# Booster_TOP.net
KiCad netlist of a schematic drawn in Altium Designer
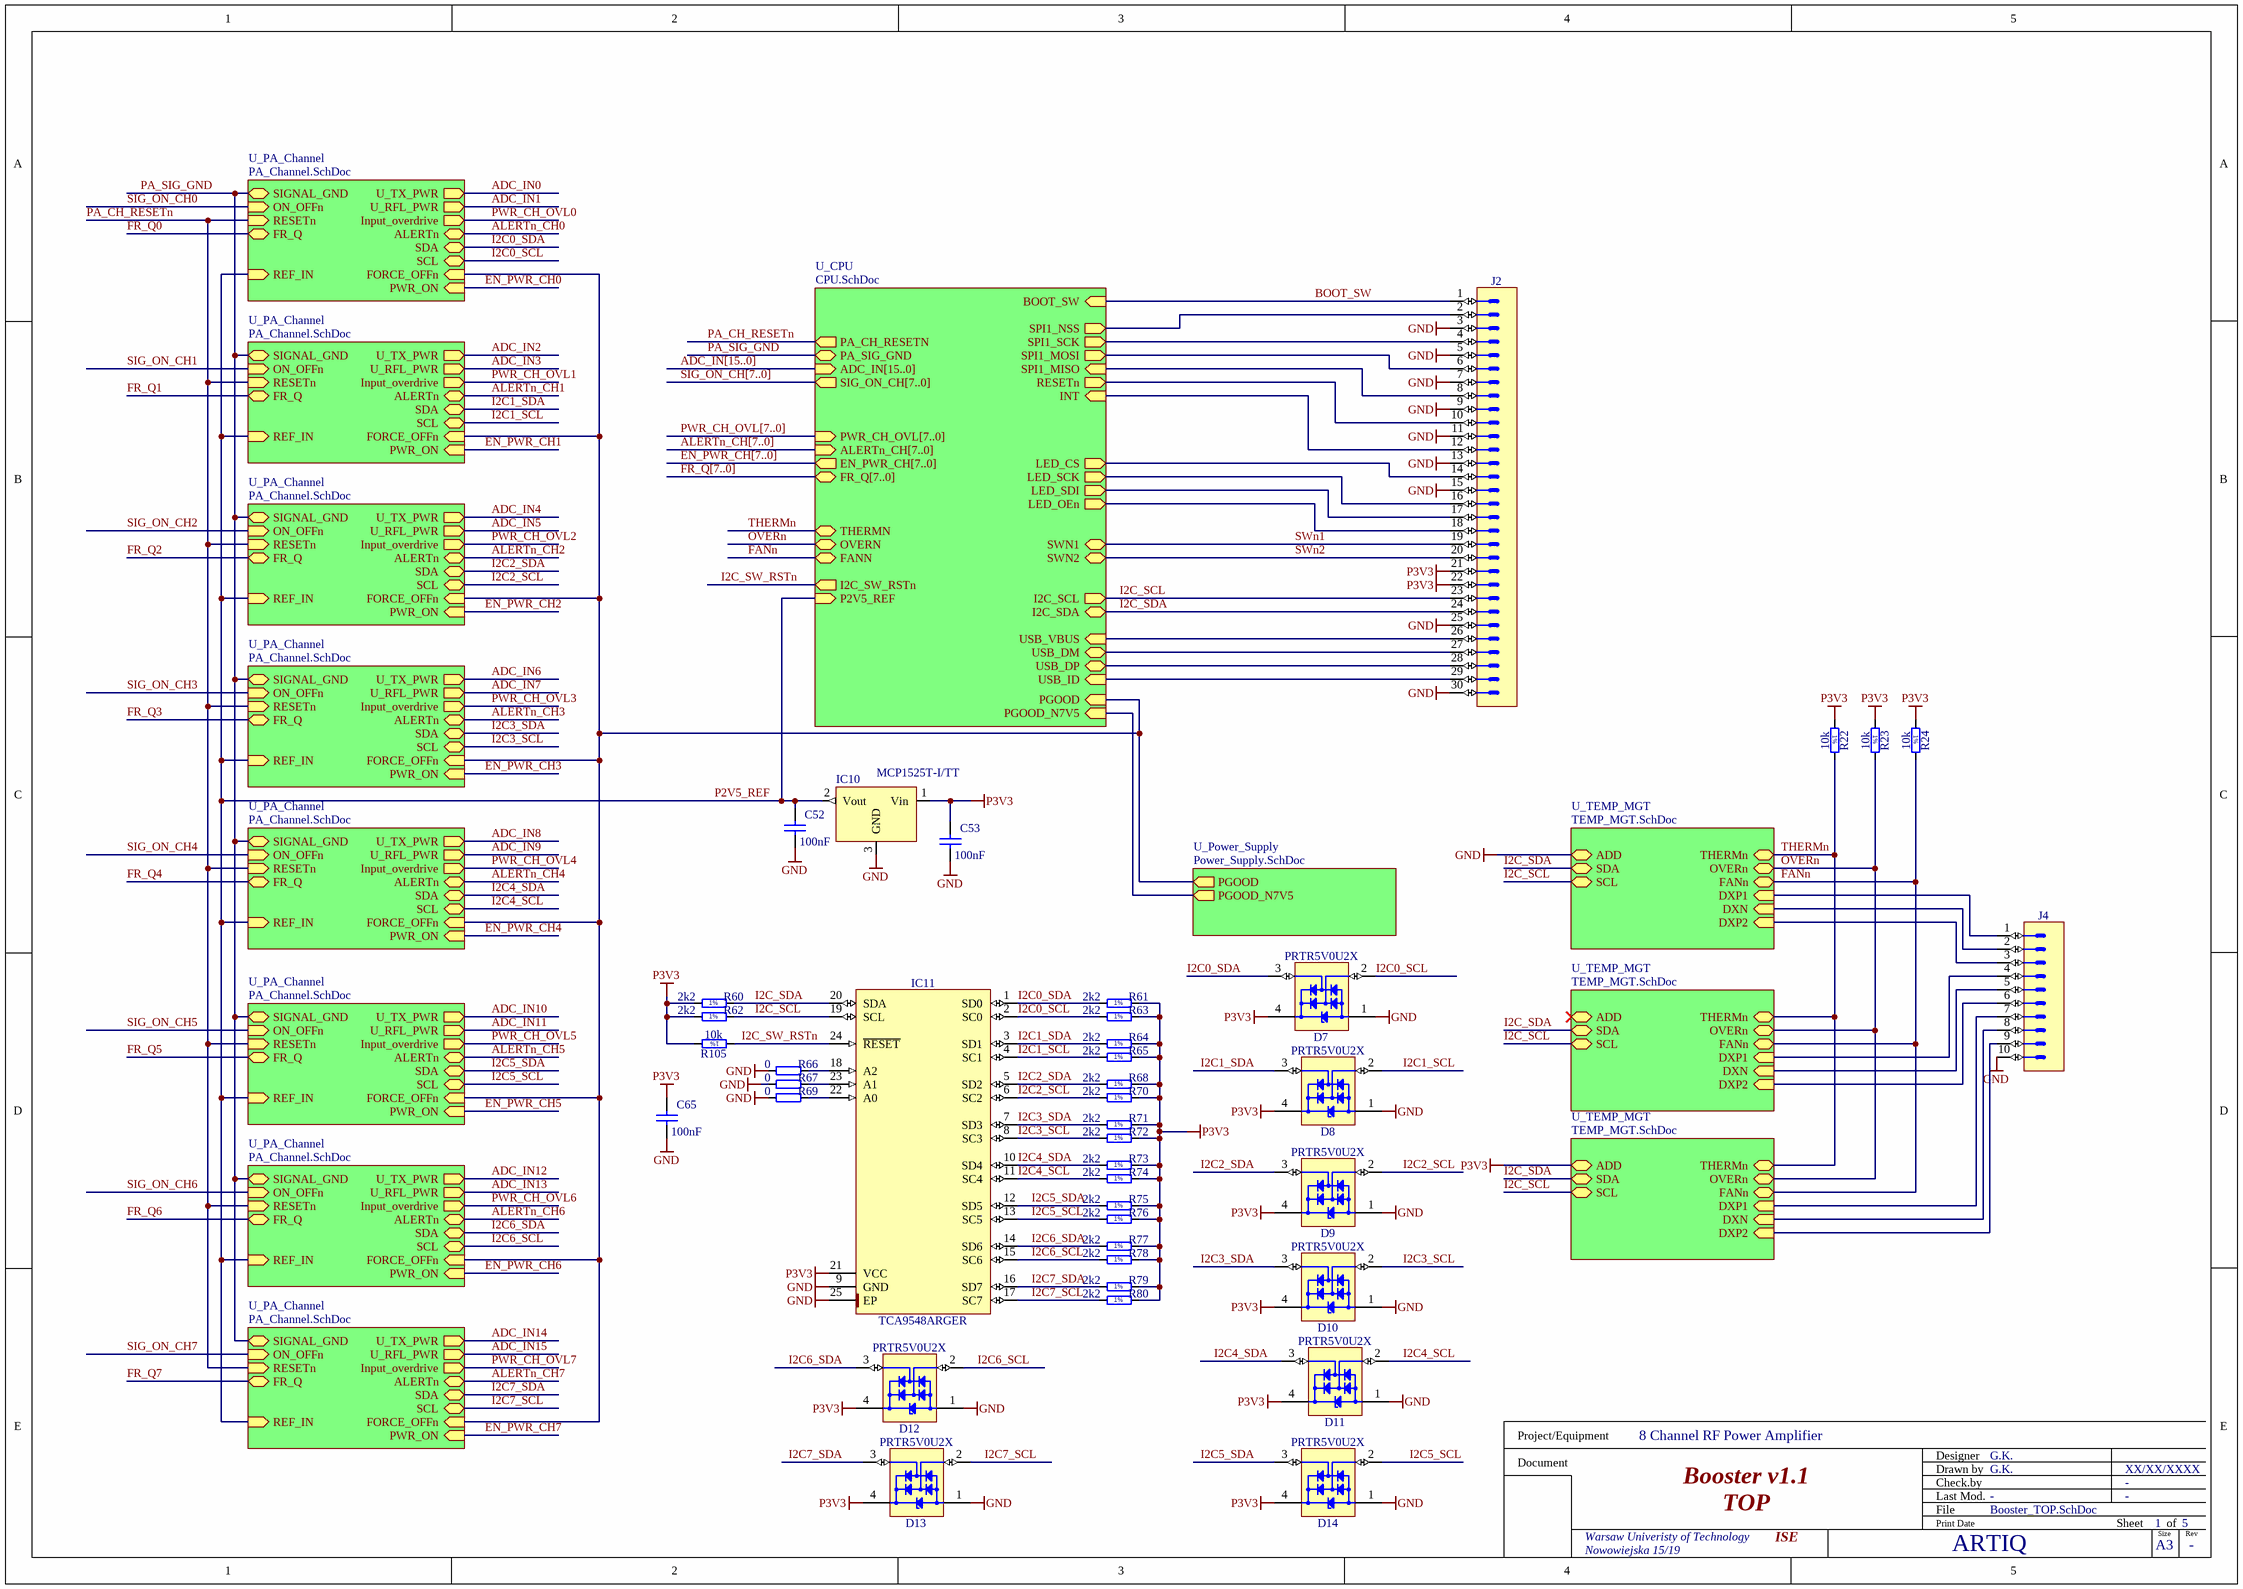
[diagram p0: Booster_TOP.SchDoc]

(export (version "E")
  (design (tool "Eeschema 10.0.6"))
  (components
    (comp (ref "C52")
      (value "100nF")
      (footprint "CAPC1005X55N")
      (description "Non-polarised capacitor")
      (fields
        (field (name "PART NUMBER") "CC0402_100NF_16V_10%_X7R")
        (field (name "VOLTAGE") "16V")
        (field (name "AUTHOR") "CERN DEM JLC")
      )
      (libsource (lib "Capacitors") (part "Capacitor - non polarized"))
    )
    (comp (ref "C53")
      (value "100nF")
      (footprint "CAPC1005X55N")
      (description "Non-polarised capacitor")
      (fields
        (field (name "PART NUMBER") "CC0402_100NF_16V_10%_X7R")
        (field (name "VOLTAGE") "16V")
        (field (name "AUTHOR") "CERN DEM JLC")
      )
      (libsource (lib "Capacitors") (part "Capacitor - non polarized"))
    )
    (comp (ref "C65")
      (value "100nF")
      (footprint "CAPC1005X55N")
      (description "Non-polarised capacitor")
      (fields
        (field (name "PART NUMBER") "CC0402_100NF_16V_10%_X7R")
        (field (name "VOLTAGE") "16V")
        (field (name "AUTHOR") "CERN DEM JLC")
      )
      (libsource (lib "Capacitors") (part "Capacitor - non polarized"))
    )
    (comp (ref "D7")
      (value "PRTR5V0U2X")
      (footprint "SOT190P230X110-4N")
      (description "Ultra Low Capacitance Double Rail-to-Rail ESD Protection Diode")
      (fields
        (field (name "VOLTAGE") "5.5V")
        (field (name "MANUFACTURER") "NXP SEMICONDUCTORS")
        (field (name "AUTHOR") "CERN DEM JLC")
      )
      (libsource (lib "ICs And Semiconductors") (part "PRTR5V0U2X"))
    )
    (comp (ref "D8")
      (value "PRTR5V0U2X")
      (footprint "SOT190P230X110-4N")
      (description "Ultra Low Capacitance Double Rail-to-Rail ESD Protection Diode")
      (fields
        (field (name "VOLTAGE") "5.5V")
        (field (name "MANUFACTURER") "NXP SEMICONDUCTORS")
        (field (name "AUTHOR") "CERN DEM JLC")
      )
      (libsource (lib "ICs And Semiconductors") (part "PRTR5V0U2X"))
    )
    (comp (ref "D9")
      (value "PRTR5V0U2X")
      (footprint "SOT190P230X110-4N")
      (description "Ultra Low Capacitance Double Rail-to-Rail ESD Protection Diode")
      (fields
        (field (name "VOLTAGE") "5.5V")
        (field (name "MANUFACTURER") "NXP SEMICONDUCTORS")
        (field (name "AUTHOR") "CERN DEM JLC")
      )
      (libsource (lib "ICs And Semiconductors") (part "PRTR5V0U2X"))
    )
    (comp (ref "D10")
      (value "PRTR5V0U2X")
      (footprint "SOT190P230X110-4N")
      (description "Ultra Low Capacitance Double Rail-to-Rail ESD Protection Diode")
      (fields
        (field (name "VOLTAGE") "5.5V")
        (field (name "MANUFACTURER") "NXP SEMICONDUCTORS")
        (field (name "AUTHOR") "CERN DEM JLC")
      )
      (libsource (lib "ICs And Semiconductors") (part "PRTR5V0U2X"))
    )
    (comp (ref "D11")
      (value "PRTR5V0U2X")
      (footprint "SOT190P230X110-4N")
      (description "Ultra Low Capacitance Double Rail-to-Rail ESD Protection Diode")
      (fields
        (field (name "VOLTAGE") "5.5V")
        (field (name "MANUFACTURER") "NXP SEMICONDUCTORS")
        (field (name "AUTHOR") "CERN DEM JLC")
      )
      (libsource (lib "ICs And Semiconductors") (part "PRTR5V0U2X"))
    )
    (comp (ref "D12")
      (value "PRTR5V0U2X")
      (footprint "SOT190P230X110-4N")
      (description "Ultra Low Capacitance Double Rail-to-Rail ESD Protection Diode")
      (fields
        (field (name "VOLTAGE") "5.5V")
        (field (name "MANUFACTURER") "NXP SEMICONDUCTORS")
        (field (name "AUTHOR") "CERN DEM JLC")
      )
      (libsource (lib "ICs And Semiconductors") (part "PRTR5V0U2X"))
    )
    (comp (ref "D13")
      (value "PRTR5V0U2X")
      (footprint "SOT190P230X110-4N")
      (description "Ultra Low Capacitance Double Rail-to-Rail ESD Protection Diode")
      (fields
        (field (name "VOLTAGE") "5.5V")
        (field (name "MANUFACTURER") "NXP SEMICONDUCTORS")
        (field (name "AUTHOR") "CERN DEM JLC")
      )
      (libsource (lib "ICs And Semiconductors") (part "PRTR5V0U2X"))
    )
    (comp (ref "D14")
      (value "PRTR5V0U2X")
      (footprint "SOT190P230X110-4N")
      (description "Ultra Low Capacitance Double Rail-to-Rail ESD Protection Diode")
      (fields
        (field (name "VOLTAGE") "5.5V")
        (field (name "MANUFACTURER") "NXP SEMICONDUCTORS")
        (field (name "AUTHOR") "CERN DEM JLC")
      )
      (libsource (lib "ICs And Semiconductors") (part "PRTR5V0U2X"))
    )
    (comp (ref "IC10")
      (value "MCP1525T-I/TT")
      (footprint "SOT95P251X112-3N")
      (description "2.5 voltage reference")
      (libsource (lib "LIBRARY_SCH") (part "REF_MCP1525"))
    )
    (comp (ref "IC11")
      (value "TCA9548ARGER")
      (footprint "QFN50P400X400X100-25N-S220")
      (description "Low Voltage 8-Channel I2C Switch With Reset")
      (fields (field (name "MANUFACTURER") "TEXAS INSTRUMENTS") (field (name "AUTHOR") "CERN DEM JLC"))
      (libsource (lib "ICs And Semiconductors") (part "TCA9548ARGER"))
    )
    (comp (ref "J2")
      (value "~")
      (footprint "3M_N2530-6002RB")
      (description "Connector 30 Male")
      (fields
        (field (name "PART NUMBER") "3M_N2530-6002RB")
        (field (name "MANUFACTURER") "3M")
        (field (name "AUTHOR") "CERN DEM JLC")
      )
      (libsource (lib "Connectors") (part "Connector 30 Male"))
    )
    (comp (ref "J4")
      (value "Header 10")
      (footprint "3M_N2510-6003RB")
      (description "Connector 10 Male")
      (fields
        (field (name "PART NUMBER") "3M_N2510-6003RB")
        (field (name "MANUFACTURER") "3M")
        (field (name "AUTHOR") "CERN DEM JLC")
      )
      (libsource (lib "Connectors") (part "Connector 10 Male"))
    )
    (comp (ref "R22")
      (value "10k")
      (footprint "RESC1005X40N")
      (description "Resistor - 1%")
      (fields
        (field (name "PART NUMBER") "R0402_10K_1%_0.0625W_100PPM")
        (field (name "POWER") "0.0625W")
        (field (name "AUTHOR") "CERN DEM JLC")
      )
      (libsource (lib "Resistors") (part "Resistor - 1%"))
    )
    (comp (ref "R23")
      (value "10k")
      (footprint "RESC1005X40N")
      (description "Resistor - 1%")
      (fields
        (field (name "PART NUMBER") "R0402_10K_1%_0.0625W_100PPM")
        (field (name "POWER") "0.0625W")
        (field (name "AUTHOR") "CERN DEM JLC")
      )
      (libsource (lib "Resistors") (part "Resistor - 1%"))
    )
    (comp (ref "R24")
      (value "10k")
      (footprint "RESC1005X40N")
      (description "Resistor - 1%")
      (fields
        (field (name "PART NUMBER") "R0402_10K_1%_0.0625W_100PPM")
        (field (name "POWER") "0.0625W")
        (field (name "AUTHOR") "CERN DEM JLC")
      )
      (libsource (lib "Resistors") (part "Resistor - 1%"))
    )
    (comp (ref "R60")
      (value "2k2")
      (footprint "RESC1005X40N")
      (description "Resistor - 1%")
      (fields
        (field (name "PART NUMBER") "R0402_2K2_1%_0.0625W_100PPM")
        (field (name "POWER") "0.0625W")
        (field (name "AUTHOR") "CERN DEM JLC")
      )
      (libsource (lib "Resistors") (part "Resistor - 1%"))
    )
    (comp (ref "R61")
      (value "2k2")
      (footprint "RESC1005X40N")
      (description "Resistor - 1%")
      (fields
        (field (name "PART NUMBER") "R0402_2K2_1%_0.0625W_100PPM")
        (field (name "POWER") "0.0625W")
        (field (name "AUTHOR") "CERN DEM JLC")
      )
      (libsource (lib "Resistors") (part "Resistor - 1%"))
    )
    (comp (ref "R62")
      (value "2k2")
      (footprint "RESC1005X40N")
      (description "Resistor - 1%")
      (fields
        (field (name "PART NUMBER") "R0402_2K2_1%_0.0625W_100PPM")
        (field (name "POWER") "0.0625W")
        (field (name "AUTHOR") "CERN DEM JLC")
      )
      (libsource (lib "Resistors") (part "Resistor - 1%"))
    )
    (comp (ref "R63")
      (value "2k2")
      (footprint "RESC1005X40N")
      (description "Resistor - 1%")
      (fields
        (field (name "PART NUMBER") "R0402_2K2_1%_0.0625W_100PPM")
        (field (name "POWER") "0.0625W")
        (field (name "AUTHOR") "CERN DEM JLC")
      )
      (libsource (lib "Resistors") (part "Resistor - 1%"))
    )
    (comp (ref "R64")
      (value "2k2")
      (footprint "RESC1005X40N")
      (description "Resistor - 1%")
      (fields
        (field (name "PART NUMBER") "R0402_2K2_1%_0.0625W_100PPM")
        (field (name "POWER") "0.0625W")
        (field (name "AUTHOR") "CERN DEM JLC")
      )
      (libsource (lib "Resistors") (part "Resistor - 1%"))
    )
    (comp (ref "R65")
      (value "2k2")
      (footprint "RESC1005X40N")
      (description "Resistor - 1%")
      (fields
        (field (name "PART NUMBER") "R0402_2K2_1%_0.0625W_100PPM")
        (field (name "POWER") "0.0625W")
        (field (name "AUTHOR") "CERN DEM JLC")
      )
      (libsource (lib "Resistors") (part "Resistor - 1%"))
    )
    (comp (ref "R66")
      (value "0")
      (footprint "RESC1005X40N")
      (description "Resistor")
      (fields
        (field (name "PART NUMBER") "R0402_0R_JUMPER")
        (field (name "MANUFACTURER") "GENERIC")
        (field (name "AUTHOR") "CERN DEM JLC")
      )
      (libsource (lib "Resistors") (part "Resistor"))
    )
    (comp (ref "R67")
      (value "0")
      (footprint "RESC1005X40N")
      (description "Resistor")
      (fields
        (field (name "PART NUMBER") "R0402_0R_JUMPER")
        (field (name "MANUFACTURER") "GENERIC")
        (field (name "AUTHOR") "CERN DEM JLC")
      )
      (libsource (lib "Resistors") (part "Resistor"))
    )
    (comp (ref "R68")
      (value "2k2")
      (footprint "RESC1005X40N")
      (description "Resistor - 1%")
      (fields
        (field (name "PART NUMBER") "R0402_2K2_1%_0.0625W_100PPM")
        (field (name "POWER") "0.0625W")
        (field (name "AUTHOR") "CERN DEM JLC")
      )
      (libsource (lib "Resistors") (part "Resistor - 1%"))
    )
    (comp (ref "R69")
      (value "0")
      (footprint "RESC1005X40N")
      (description "Resistor")
      (fields
        (field (name "PART NUMBER") "R0402_0R_JUMPER")
        (field (name "MANUFACTURER") "GENERIC")
        (field (name "AUTHOR") "CERN DEM JLC")
      )
      (libsource (lib "Resistors") (part "Resistor"))
    )
    (comp (ref "R70")
      (value "2k2")
      (footprint "RESC1005X40N")
      (description "Resistor - 1%")
      (fields
        (field (name "PART NUMBER") "R0402_2K2_1%_0.0625W_100PPM")
        (field (name "POWER") "0.0625W")
        (field (name "AUTHOR") "CERN DEM JLC")
      )
      (libsource (lib "Resistors") (part "Resistor - 1%"))
    )
    (comp (ref "R71")
      (value "2k2")
      (footprint "RESC1005X40N")
      (description "Resistor - 1%")
      (fields
        (field (name "PART NUMBER") "R0402_2K2_1%_0.0625W_100PPM")
        (field (name "POWER") "0.0625W")
        (field (name "AUTHOR") "CERN DEM JLC")
      )
      (libsource (lib "Resistors") (part "Resistor - 1%"))
    )
    (comp (ref "R72")
      (value "2k2")
      (footprint "RESC1005X40N")
      (description "Resistor - 1%")
      (fields
        (field (name "PART NUMBER") "R0402_2K2_1%_0.0625W_100PPM")
        (field (name "POWER") "0.0625W")
        (field (name "AUTHOR") "CERN DEM JLC")
      )
      (libsource (lib "Resistors") (part "Resistor - 1%"))
    )
    (comp (ref "R73")
      (value "2k2")
      (footprint "RESC1005X40N")
      (description "Resistor - 1%")
      (fields
        (field (name "PART NUMBER") "R0402_2K2_1%_0.0625W_100PPM")
        (field (name "POWER") "0.0625W")
        (field (name "AUTHOR") "CERN DEM JLC")
      )
      (libsource (lib "Resistors") (part "Resistor - 1%"))
    )
    (comp (ref "R74")
      (value "2k2")
      (footprint "RESC1005X40N")
      (description "Resistor - 1%")
      (fields
        (field (name "PART NUMBER") "R0402_2K2_1%_0.0625W_100PPM")
        (field (name "POWER") "0.0625W")
        (field (name "AUTHOR") "CERN DEM JLC")
      )
      (libsource (lib "Resistors") (part "Resistor - 1%"))
    )
    (comp (ref "R75")
      (value "2k2")
      (footprint "RESC1005X40N")
      (description "Resistor - 1%")
      (fields
        (field (name "PART NUMBER") "R0402_2K2_1%_0.0625W_100PPM")
        (field (name "POWER") "0.0625W")
        (field (name "AUTHOR") "CERN DEM JLC")
      )
      (libsource (lib "Resistors") (part "Resistor - 1%"))
    )
    (comp (ref "R76")
      (value "2k2")
      (footprint "RESC1005X40N")
      (description "Resistor - 1%")
      (fields
        (field (name "PART NUMBER") "R0402_2K2_1%_0.0625W_100PPM")
        (field (name "POWER") "0.0625W")
        (field (name "AUTHOR") "CERN DEM JLC")
      )
      (libsource (lib "Resistors") (part "Resistor - 1%"))
    )
    (comp (ref "R77")
      (value "2k2")
      (footprint "RESC1005X40N")
      (description "Resistor - 1%")
      (fields
        (field (name "PART NUMBER") "R0402_2K2_1%_0.0625W_100PPM")
        (field (name "POWER") "0.0625W")
        (field (name "AUTHOR") "CERN DEM JLC")
      )
      (libsource (lib "Resistors") (part "Resistor - 1%"))
    )
    (comp (ref "R78")
      (value "2k2")
      (footprint "RESC1005X40N")
      (description "Resistor - 1%")
      (fields
        (field (name "PART NUMBER") "R0402_2K2_1%_0.0625W_100PPM")
        (field (name "POWER") "0.0625W")
        (field (name "AUTHOR") "CERN DEM JLC")
      )
      (libsource (lib "Resistors") (part "Resistor - 1%"))
    )
    (comp (ref "R79")
      (value "2k2")
      (footprint "RESC1005X40N")
      (description "Resistor - 1%")
      (fields
        (field (name "PART NUMBER") "R0402_2K2_1%_0.0625W_100PPM")
        (field (name "POWER") "0.0625W")
        (field (name "AUTHOR") "CERN DEM JLC")
      )
      (libsource (lib "Resistors") (part "Resistor - 1%"))
    )
    (comp (ref "R80")
      (value "2k2")
      (footprint "RESC1005X40N")
      (description "Resistor - 1%")
      (fields
        (field (name "PART NUMBER") "R0402_2K2_1%_0.0625W_100PPM")
        (field (name "POWER") "0.0625W")
        (field (name "AUTHOR") "CERN DEM JLC")
      )
      (libsource (lib "Resistors") (part "Resistor - 1%"))
    )
    (comp (ref "R105")
      (value "10k")
      (footprint "RESC1005X40N")
      (description "Resistor - 1%")
      (fields
        (field (name "PART NUMBER") "R0402_10K_1%_0.0625W_100PPM")
        (field (name "POWER") "0.0625W")
        (field (name "AUTHOR") "CERN DEM JLC")
      )
      (libsource (lib "Resistors") (part "Resistor - 1%"))
    )
  )
  (nets
    (net (code "28") (name "/BOOT_SW") (class "Default")
      (node (ref "J2") (pin "1") (pinfunction "1_1") (pintype "bidirectional"))
    )
    (net (code "29") (name "/DXN") (class "Default")
      (node (ref "J4") (pin "2") (pinfunction "2_2") (pintype "bidirectional"))
    )
    (net (code "30") (name "/DXN_1") (class "Default")
      (node (ref "J4") (pin "5") (pinfunction "5_5") (pintype "bidirectional"))
    )
    (net (code "31") (name "/DXN_2") (class "Default")
      (node (ref "J4") (pin "8") (pinfunction "8_8") (pintype "bidirectional"))
    )
    (net (code "32") (name "/DXP1") (class "Default")
      (node (ref "J4") (pin "1") (pinfunction "1_1") (pintype "bidirectional"))
    )
    (net (code "33") (name "/DXP1_1") (class "Default")
      (node (ref "J4") (pin "4") (pinfunction "4_4") (pintype "bidirectional"))
    )
    (net (code "34") (name "/DXP1_2") (class "Default")
      (node (ref "J4") (pin "7") (pinfunction "7_7") (pintype "bidirectional"))
    )
    (net (code "35") (name "/DXP2") (class "Default")
      (node (ref "J4") (pin "3") (pinfunction "3_3") (pintype "bidirectional"))
    )
    (net (code "36") (name "/DXP2_1") (class "Default")
      (node (ref "J4") (pin "6") (pinfunction "6_6") (pintype "bidirectional"))
    )
    (net (code "37") (name "/DXP2_2") (class "Default")
      (node (ref "J4") (pin "9") (pinfunction "9_9") (pintype "bidirectional"))
    )
    (net (code "47") (name "/FANn") (class "Default")
      (node (ref "R24") (pin "2") (pinfunction "2_2") (pintype "passive"))
    )
    (net (code "57") (name "/I2C0_SCL") (class "Default")
      (node (ref "D7") (pin "2") (pinfunction "I/O1_2") (pintype "bidirectional"))
      (node (ref "IC11") (pin "2") (pinfunction "SC0_2") (pintype "bidirectional"))
      (node (ref "R63") (pin "1") (pinfunction "1_1") (pintype "passive"))
    )
    (net (code "58") (name "/I2C0_SDA") (class "Default")
      (node (ref "D7") (pin "3") (pinfunction "I/O2_3") (pintype "bidirectional"))
      (node (ref "IC11") (pin "1") (pinfunction "SD0_1") (pintype "bidirectional"))
      (node (ref "R61") (pin "1") (pinfunction "1_1") (pintype "passive"))
    )
    (net (code "59") (name "/I2C1_SCL") (class "Default")
      (node (ref "D8") (pin "2") (pinfunction "I/O1_2") (pintype "bidirectional"))
      (node (ref "IC11") (pin "4") (pinfunction "SC1_4") (pintype "bidirectional"))
      (node (ref "R65") (pin "1") (pinfunction "1_1") (pintype "passive"))
    )
    (net (code "60") (name "/I2C1_SDA") (class "Default")
      (node (ref "D8") (pin "3") (pinfunction "I/O2_3") (pintype "bidirectional"))
      (node (ref "IC11") (pin "3") (pinfunction "SD1_3") (pintype "bidirectional"))
      (node (ref "R64") (pin "1") (pinfunction "1_1") (pintype "passive"))
    )
    (net (code "61") (name "/I2C2_SCL") (class "Default")
      (node (ref "D9") (pin "2") (pinfunction "I/O1_2") (pintype "bidirectional"))
      (node (ref "IC11") (pin "6") (pinfunction "SC2_6") (pintype "bidirectional"))
      (node (ref "R70") (pin "1") (pinfunction "1_1") (pintype "passive"))
    )
    (net (code "62") (name "/I2C2_SDA") (class "Default")
      (node (ref "D9") (pin "3") (pinfunction "I/O2_3") (pintype "bidirectional"))
      (node (ref "IC11") (pin "5") (pinfunction "SD2_5") (pintype "bidirectional"))
      (node (ref "R68") (pin "1") (pinfunction "1_1") (pintype "passive"))
    )
    (net (code "63") (name "/I2C3_SCL") (class "Default")
      (node (ref "D10") (pin "2") (pinfunction "I/O1_2") (pintype "bidirectional"))
      (node (ref "IC11") (pin "8") (pinfunction "SC3_8") (pintype "bidirectional"))
      (node (ref "R72") (pin "1") (pinfunction "1_1") (pintype "passive"))
    )
    (net (code "64") (name "/I2C3_SDA") (class "Default")
      (node (ref "D10") (pin "3") (pinfunction "I/O2_3") (pintype "bidirectional"))
      (node (ref "IC11") (pin "7") (pinfunction "SD3_7") (pintype "bidirectional"))
      (node (ref "R71") (pin "1") (pinfunction "1_1") (pintype "passive"))
    )
    (net (code "65") (name "/I2C4_SCL") (class "Default")
      (node (ref "D11") (pin "2") (pinfunction "I/O1_2") (pintype "bidirectional"))
      (node (ref "IC11") (pin "11") (pinfunction "SC4_11") (pintype "bidirectional"))
      (node (ref "R74") (pin "1") (pinfunction "1_1") (pintype "passive"))
    )
    (net (code "66") (name "/I2C4_SDA") (class "Default")
      (node (ref "D11") (pin "3") (pinfunction "I/O2_3") (pintype "bidirectional"))
      (node (ref "IC11") (pin "10") (pinfunction "SD4_10") (pintype "bidirectional"))
      (node (ref "R73") (pin "1") (pinfunction "1_1") (pintype "passive"))
    )
    (net (code "67") (name "/I2C5_SCL") (class "Default")
      (node (ref "D14") (pin "2") (pinfunction "I/O1_2") (pintype "bidirectional"))
      (node (ref "IC11") (pin "13") (pinfunction "SC5_13") (pintype "bidirectional"))
      (node (ref "R76") (pin "1") (pinfunction "1_1") (pintype "passive"))
    )
    (net (code "68") (name "/I2C5_SDA") (class "Default")
      (node (ref "D14") (pin "3") (pinfunction "I/O2_3") (pintype "bidirectional"))
      (node (ref "IC11") (pin "12") (pinfunction "SD5_12") (pintype "bidirectional"))
      (node (ref "R75") (pin "1") (pinfunction "1_1") (pintype "passive"))
    )
    (net (code "69") (name "/I2C6_SCL") (class "Default")
      (node (ref "D12") (pin "2") (pinfunction "I/O1_2") (pintype "bidirectional"))
      (node (ref "IC11") (pin "15") (pinfunction "SC6_15") (pintype "bidirectional"))
      (node (ref "R78") (pin "1") (pinfunction "1_1") (pintype "passive"))
    )
    (net (code "70") (name "/I2C6_SDA") (class "Default")
      (node (ref "D12") (pin "3") (pinfunction "I/O2_3") (pintype "bidirectional"))
      (node (ref "IC11") (pin "14") (pinfunction "SD6_14") (pintype "bidirectional"))
      (node (ref "R77") (pin "1") (pinfunction "1_1") (pintype "passive"))
    )
    (net (code "71") (name "/I2C7_SCL") (class "Default")
      (node (ref "D13") (pin "2") (pinfunction "I/O1_2") (pintype "bidirectional"))
      (node (ref "IC11") (pin "17") (pinfunction "SC7_17") (pintype "bidirectional"))
      (node (ref "R80") (pin "1") (pinfunction "1_1") (pintype "passive"))
    )
    (net (code "72") (name "/I2C7_SDA") (class "Default")
      (node (ref "D13") (pin "3") (pinfunction "I/O2_3") (pintype "bidirectional"))
      (node (ref "IC11") (pin "16") (pinfunction "SD7_16") (pintype "bidirectional"))
      (node (ref "R79") (pin "1") (pinfunction "1_1") (pintype "passive"))
    )
    (net (code "73") (name "/I2C_SCL") (class "Default")
      (node (ref "IC11") (pin "19") (pinfunction "SCL_19") (pintype "bidirectional"))
      (node (ref "J2") (pin "23") (pinfunction "23_23") (pintype "bidirectional"))
      (node (ref "R62") (pin "2") (pinfunction "2_2") (pintype "passive"))
    )
    (net (code "74") (name "/I2C_SDA") (class "Default")
      (node (ref "IC11") (pin "20") (pinfunction "SDA_20") (pintype "bidirectional"))
      (node (ref "J2") (pin "24") (pinfunction "24_24") (pintype "bidirectional"))
      (node (ref "R60") (pin "2") (pinfunction "2_2") (pintype "passive"))
    )
    (net (code "75") (name "/I2C_SW_RSTn") (class "Default")
      (node (ref "IC11") (pin "24") (pinfunction "~{RESET}_24") (pintype "input"))
      (node (ref "R105") (pin "1") (pinfunction "1_1") (pintype "passive"))
    )
    (net (code "76") (name "/INT") (class "Default")
      (node (ref "J2") (pin "12") (pinfunction "12_12") (pintype "bidirectional"))
    )
    (net (code "77") (name "/LED_CS") (class "Default")
      (node (ref "J2") (pin "14") (pinfunction "14_14") (pintype "bidirectional"))
    )
    (net (code "78") (name "/LED_OEn") (class "Default")
      (node (ref "J2") (pin "18") (pinfunction "18_18") (pintype "bidirectional"))
    )
    (net (code "79") (name "/LED_SCK") (class "Default")
      (node (ref "J2") (pin "16") (pinfunction "16_16") (pintype "bidirectional"))
    )
    (net (code "80") (name "/LED_SDI") (class "Default")
      (node (ref "J2") (pin "17") (pinfunction "17_17") (pintype "bidirectional"))
    )
    (net (code "81") (name "/OVERn") (class "Default")
      (node (ref "R23") (pin "2") (pinfunction "2_2") (pintype "passive"))
    )
    (net (code "82") (name "/P2V5_REF") (class "Default")
      (node (ref "C52") (pin "1") (pinfunction "1_1") (pintype "passive"))
      (node (ref "IC10") (pin "2") (pinfunction "Vout_2") (pintype "output"))
    )
    (net (code "96") (name "/RESETn") (class "Default")
      (node (ref "J2") (pin "10") (pinfunction "10_10") (pintype "bidirectional"))
    )
    (net (code "106") (name "/SPI1_MISO") (class "Default")
      (node (ref "J2") (pin "8") (pinfunction "8_8") (pintype "bidirectional"))
    )
    (net (code "107") (name "/SPI1_MOSI") (class "Default")
      (node (ref "J2") (pin "6") (pinfunction "6_6") (pintype "bidirectional"))
    )
    (net (code "108") (name "/SPI1_NSS") (class "Default")
      (node (ref "J2") (pin "2") (pinfunction "2_2") (pintype "bidirectional"))
    )
    (net (code "109") (name "/SPI1_SCK") (class "Default")
      (node (ref "J2") (pin "4") (pinfunction "4_4") (pintype "bidirectional"))
    )
    (net (code "110") (name "/SWn1") (class "Default")
      (node (ref "J2") (pin "19") (pinfunction "19_19") (pintype "bidirectional"))
    )
    (net (code "111") (name "/SWn2") (class "Default")
      (node (ref "J2") (pin "20") (pinfunction "20_20") (pintype "bidirectional"))
    )
    (net (code "112") (name "/THERMn") (class "Default")
      (node (ref "R22") (pin "2") (pinfunction "2_2") (pintype "passive"))
    )
    (net (code "113") (name "/USB_DM") (class "Default")
      (node (ref "J2") (pin "27") (pinfunction "27_27") (pintype "bidirectional"))
    )
    (net (code "114") (name "/USB_DP") (class "Default")
      (node (ref "J2") (pin "28") (pinfunction "28_28") (pintype "bidirectional"))
    )
    (net (code "115") (name "/USB_ID") (class "Default")
      (node (ref "J2") (pin "29") (pinfunction "29_29") (pintype "bidirectional"))
    )
    (net (code "116") (name "/USB_VBUS") (class "Default")
      (node (ref "J2") (pin "26") (pinfunction "26_26") (pintype "bidirectional"))
    )
    (net (code "117") (name "GND") (class "Default")
      (node (ref "C52") (pin "2") (pinfunction "2_2") (pintype "passive"))
      (node (ref "C53") (pin "2") (pinfunction "2_2") (pintype "passive"))
      (node (ref "C65") (pin "2") (pinfunction "2_2") (pintype "passive"))
      (node (ref "D10") (pin "1") (pinfunction "GND_1") (pintype "power_in"))
      (node (ref "D11") (pin "1") (pinfunction "GND_1") (pintype "power_in"))
      (node (ref "D12") (pin "1") (pinfunction "GND_1") (pintype "power_in"))
      (node (ref "D13") (pin "1") (pinfunction "GND_1") (pintype "power_in"))
      (node (ref "D14") (pin "1") (pinfunction "GND_1") (pintype "power_in"))
      (node (ref "D7") (pin "1") (pinfunction "GND_1") (pintype "power_in"))
      (node (ref "D8") (pin "1") (pinfunction "GND_1") (pintype "power_in"))
      (node (ref "D9") (pin "1") (pinfunction "GND_1") (pintype "power_in"))
      (node (ref "IC10") (pin "3") (pinfunction "GND_3") (pintype "power_in"))
      (node (ref "IC11") (pin "25") (pinfunction "EP_25") (pintype "power_in"))
      (node (ref "IC11") (pin "9") (pinfunction "GND_9") (pintype "power_in"))
      (node (ref "J2") (pin "11") (pinfunction "11_11") (pintype "bidirectional"))
      (node (ref "J2") (pin "13") (pinfunction "13_13") (pintype "bidirectional"))
      (node (ref "J2") (pin "15") (pinfunction "15_15") (pintype "bidirectional"))
      (node (ref "J2") (pin "25") (pinfunction "25_25") (pintype "bidirectional"))
      (node (ref "J2") (pin "3") (pinfunction "3_3") (pintype "bidirectional"))
      (node (ref "J2") (pin "30") (pinfunction "30_30") (pintype "bidirectional"))
      (node (ref "J2") (pin "5") (pinfunction "5_5") (pintype "bidirectional"))
      (node (ref "J2") (pin "7") (pinfunction "7_7") (pintype "bidirectional"))
      (node (ref "J2") (pin "9") (pinfunction "9_9") (pintype "bidirectional"))
      (node (ref "J4") (pin "10") (pinfunction "10_10") (pintype "bidirectional"))
      (node (ref "R66") (pin "1") (pinfunction "1_1") (pintype "passive"))
      (node (ref "R67") (pin "1") (pinfunction "1_1") (pintype "passive"))
      (node (ref "R69") (pin "1") (pinfunction "1_1") (pintype "passive"))
    )
    (net (code "118") (name "Net-(IC11-A0)") (class "Default")
      (node (ref "IC11") (pin "22") (pinfunction "A0_22") (pintype "input"))
      (node (ref "R69") (pin "2") (pinfunction "2_2") (pintype "passive"))
    )
    (net (code "119") (name "Net-(IC11-A1)") (class "Default")
      (node (ref "IC11") (pin "23") (pinfunction "A1_23") (pintype "input"))
      (node (ref "R67") (pin "2") (pinfunction "2_2") (pintype "passive"))
    )
    (net (code "120") (name "Net-(IC11-A2)") (class "Default")
      (node (ref "IC11") (pin "18") (pinfunction "A2_18") (pintype "input"))
      (node (ref "R66") (pin "2") (pinfunction "2_2") (pintype "passive"))
    )
    (net (code "121") (name "P3V3") (class "Default")
      (node (ref "C53") (pin "1") (pinfunction "1_1") (pintype "passive"))
      (node (ref "C65") (pin "1") (pinfunction "1_1") (pintype "passive"))
      (node (ref "D10") (pin "4") (pinfunction "VCC_4") (pintype "power_in"))
      (node (ref "D11") (pin "4") (pinfunction "VCC_4") (pintype "power_in"))
      (node (ref "D12") (pin "4") (pinfunction "VCC_4") (pintype "power_in"))
      (node (ref "D13") (pin "4") (pinfunction "VCC_4") (pintype "power_in"))
      (node (ref "D14") (pin "4") (pinfunction "VCC_4") (pintype "power_in"))
      (node (ref "D7") (pin "4") (pinfunction "VCC_4") (pintype "power_in"))
      (node (ref "D8") (pin "4") (pinfunction "VCC_4") (pintype "power_in"))
      (node (ref "D9") (pin "4") (pinfunction "VCC_4") (pintype "power_in"))
      (node (ref "IC10") (pin "1") (pinfunction "Vin_1") (pintype "power_in"))
      (node (ref "IC11") (pin "21") (pinfunction "VCC_21") (pintype "power_in"))
      (node (ref "J2") (pin "21") (pinfunction "21_21") (pintype "bidirectional"))
      (node (ref "J2") (pin "22") (pinfunction "22_22") (pintype "bidirectional"))
      (node (ref "R105") (pin "2") (pinfunction "2_2") (pintype "passive"))
      (node (ref "R22") (pin "1") (pinfunction "1_1") (pintype "passive"))
      (node (ref "R23") (pin "1") (pinfunction "1_1") (pintype "passive"))
      (node (ref "R24") (pin "1") (pinfunction "1_1") (pintype "passive"))
      (node (ref "R60") (pin "1") (pinfunction "1_1") (pintype "passive"))
      (node (ref "R61") (pin "2") (pinfunction "2_2") (pintype "passive"))
      (node (ref "R62") (pin "1") (pinfunction "1_1") (pintype "passive"))
      (node (ref "R63") (pin "2") (pinfunction "2_2") (pintype "passive"))
      (node (ref "R64") (pin "2") (pinfunction "2_2") (pintype "passive"))
      (node (ref "R65") (pin "2") (pinfunction "2_2") (pintype "passive"))
      (node (ref "R68") (pin "2") (pinfunction "2_2") (pintype "passive"))
      (node (ref "R70") (pin "2") (pinfunction "2_2") (pintype "passive"))
      (node (ref "R71") (pin "2") (pinfunction "2_2") (pintype "passive"))
      (node (ref "R72") (pin "2") (pinfunction "2_2") (pintype "passive"))
      (node (ref "R73") (pin "2") (pinfunction "2_2") (pintype "passive"))
      (node (ref "R74") (pin "2") (pinfunction "2_2") (pintype "passive"))
      (node (ref "R75") (pin "2") (pinfunction "2_2") (pintype "passive"))
      (node (ref "R76") (pin "2") (pinfunction "2_2") (pintype "passive"))
      (node (ref "R77") (pin "2") (pinfunction "2_2") (pintype "passive"))
      (node (ref "R78") (pin "2") (pinfunction "2_2") (pintype "passive"))
      (node (ref "R79") (pin "2") (pinfunction "2_2") (pintype "passive"))
      (node (ref "R80") (pin "2") (pinfunction "2_2") (pintype "passive"))
    )
  )
)
